# tnychron_1_3.net
KiCad netlist of a schematic drawn in EAGLE
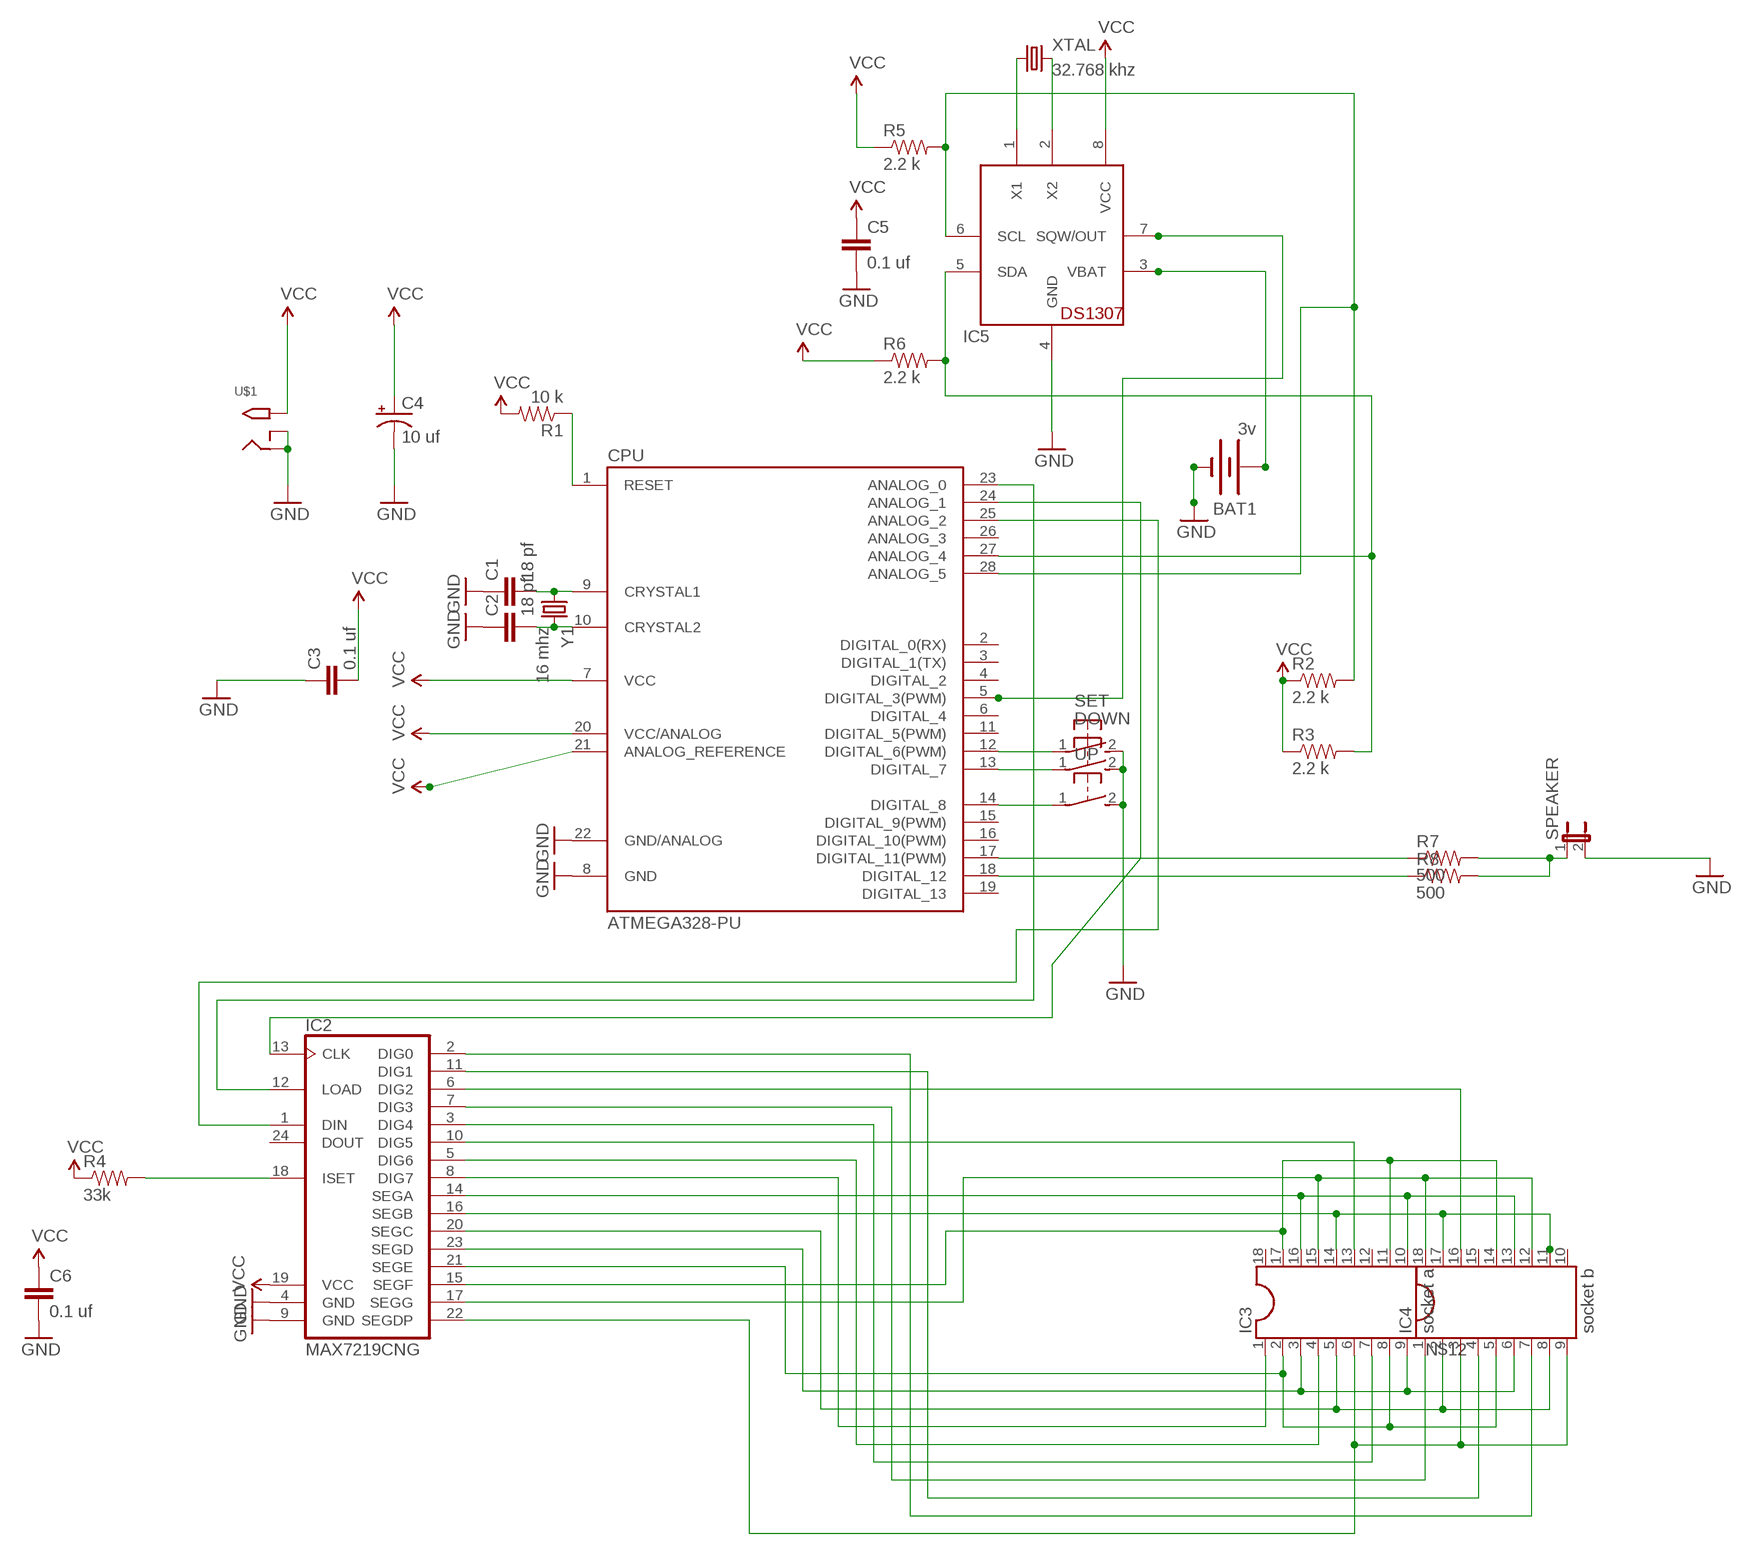
[diagram p0: schematic, sheet 1]

(export (version "E")
  (design (tool "Eeschema 10.0.6"))
  (components
    (comp (ref "BAT1")
      (value "3v")
      (footprint "eagle-import:BATTCON_12MM_PTH")
      (libsource (lib "eagle-import") (part "BATTERY12PTH"))
    )
    (comp (ref "C1")
      (value "18 pf")
      (footprint "eagle-import:CAP-PTH-SMALL2")
      (libsource (lib "eagle-import") (part "CAPPTH2"))
    )
    (comp (ref "C2")
      (value "18 pf")
      (footprint "eagle-import:CAP-PTH-SMALL2")
      (libsource (lib "eagle-import") (part "CAPPTH2"))
    )
    (comp (ref "C3")
      (value "0.1 uf")
      (footprint "eagle-import:CAP-PTH-SMALL2")
      (libsource (lib "eagle-import") (part "CAPPTH2"))
    )
    (comp (ref "C4")
      (value "10 uf")
      (footprint "eagle-import:CPOL-RADIAL-10UF-25V")
      (libsource (lib "eagle-import") (part "CAP_POLPTH2"))
    )
    (comp (ref "C5")
      (value "0.1 uf")
      (footprint "eagle-import:CAP-PTH-SMALL2")
      (libsource (lib "eagle-import") (part "CAPPTH2"))
    )
    (comp (ref "C6")
      (value "0.1 uf")
      (footprint "eagle-import:CAP-PTH-SMALL2")
      (libsource (lib "eagle-import") (part "CAPPTH2"))
    )
    (comp (ref "CPU")
      (value "ATMEGA328-PU")
      (footprint "eagle-import:DIL28-3")
      (libsource (lib "eagle-import") (part "ATMEGA168-PU"))
    )
    (comp (ref "DOWN")
      (value "31-XX")
      (footprint "eagle-import:B3F-31XX")
      (libsource (lib "eagle-import") (part "31-XX"))
    )
    (comp (ref "IC2")
      (value "MAX7219CNG")
      (footprint "eagle-import:DIL24-3")
      (fields (field (name "MF") "MAXIM"))
      (libsource (lib "eagle-import") (part "MAX7219CNG"))
    )
    (comp (ref "IC3")
      (value "socket a")
      (footprint "eagle-import:DIL18")
      (libsource (lib "eagle-import") (part "DIL18"))
    )
    (comp (ref "IC4")
      (value "socket b")
      (footprint "eagle-import:DIL18")
      (libsource (lib "eagle-import") (part "DIL18"))
    )
    (comp (ref "IC5")
      (value "DS1307")
      (footprint "eagle-import:DIL08")
      (libsource (lib "eagle-import") (part "DS1307"))
    )
    (comp (ref "R1")
      (value "10 k")
      (footprint "eagle-import:AXIAL-0.4")
      (libsource (lib "eagle-import") (part "RESISTORPTH-1/4W"))
    )
    (comp (ref "R2")
      (value "2.2 k")
      (footprint "eagle-import:AXIAL-0.4")
      (libsource (lib "eagle-import") (part "RESISTORPTH-1/4W"))
    )
    (comp (ref "R3")
      (value "2.2 k")
      (footprint "eagle-import:AXIAL-0.4")
      (libsource (lib "eagle-import") (part "RESISTORPTH-1/4W"))
    )
    (comp (ref "R4")
      (value "33k")
      (footprint "eagle-import:AXIAL-0.4")
      (libsource (lib "eagle-import") (part "RESISTORPTH-1/4W"))
    )
    (comp (ref "R5")
      (value "2.2 k")
      (footprint "eagle-import:AXIAL-0.4")
      (libsource (lib "eagle-import") (part "RESISTORPTH-1/4W"))
    )
    (comp (ref "R6")
      (value "2.2 k")
      (footprint "eagle-import:AXIAL-0.4")
      (libsource (lib "eagle-import") (part "RESISTORPTH-1/4W"))
    )
    (comp (ref "R7")
      (value "500")
      (footprint "eagle-import:AXIAL-0.3")
      (libsource (lib "eagle-import") (part "RESISTORAXIAL-0.3"))
    )
    (comp (ref "R8")
      (value "500")
      (footprint "eagle-import:AXIAL-0.3")
      (libsource (lib "eagle-import") (part "RESISTORAXIAL-0.3"))
    )
    (comp (ref "SET")
      (value "31-XX")
      (footprint "eagle-import:B3F-31XX")
      (libsource (lib "eagle-import") (part "31-XX"))
    )
    (comp (ref "SPEAKER")
      (value "JUMPER-2PTH")
      (footprint "eagle-import:1X02")
      (libsource (lib "eagle-import") (part "JUMPER-2PTH"))
    )
    (comp (ref "U$1")
      (value "2.1MMJACKTHM")
      (footprint "eagle-import:PJ-102A")
      (libsource (lib "eagle-import") (part "2.1MMJACKTHM"))
    )
    (comp (ref "UP")
      (value "31-XX")
      (footprint "eagle-import:B3F-31XX")
      (libsource (lib "eagle-import") (part "31-XX"))
    )
    (comp (ref "XTAL")
      (value "32.768 khz")
      (footprint "eagle-import:TC26H")
      (libsource (lib "eagle-import") (part "CRYSTALTC26H"))
    )
    (comp (ref "Y1")
      (value "16 mhz")
      (footprint "eagle-import:HC49US")
      (libsource (lib "eagle-import") (part "CRYSTALHC49US"))
    )
  )
  (nets
    (net (code "1") (name "/N$12") (class "Default")
      (node (ref "IC2") (pin "7") (pinfunction "DIG3_7") (pintype "output"))
      (node (ref "IC4") (pin "1") (pinfunction "1_1") (pintype "passive"))
    )
    (net (code "2") (name "GND") (class "Default")
      (node (ref "BAT1") (pin "GND") (pinfunction "-_GND") (pintype "power_in"))
      (node (ref "C1") (pin "1") (pinfunction "1_1") (pintype "passive"))
      (node (ref "C2") (pin "1") (pinfunction "1_1") (pintype "passive"))
      (node (ref "C3") (pin "1") (pinfunction "1_1") (pintype "passive"))
      (node (ref "C4") (pin "2") (pinfunction "-_2") (pintype "passive"))
      (node (ref "C5") (pin "2") (pinfunction "2_2") (pintype "passive"))
      (node (ref "C6") (pin "2") (pinfunction "2_2") (pintype "passive"))
      (node (ref "CPU") (pin "22") (pinfunction "GND/ANALOG_22") (pintype "power_in"))
      (node (ref "CPU") (pin "8") (pinfunction "GND_8") (pintype "power_in"))
      (node (ref "DOWN") (pin "2") (pinfunction "S_2") (pintype "passive"))
      (node (ref "IC2") (pin "4") (pinfunction "GND_4") (pintype "power_in"))
      (node (ref "IC2") (pin "9") (pinfunction "GND_9") (pintype "power_in"))
      (node (ref "IC5") (pin "4") (pinfunction "GND_4") (pintype "power_in"))
      (node (ref "SET") (pin "2") (pinfunction "S_2") (pintype "passive"))
      (node (ref "SPEAKER") (pin "2") (pinfunction "2_2") (pintype "passive"))
      (node (ref "U$1") (pin "RING") (pinfunction "RING_RING") (pintype "bidirectional"))
      (node (ref "U$1") (pin "RING_SW") (pinfunction "RING_SW_RING_SW") (pintype "bidirectional"))
      (node (ref "UP") (pin "2") (pinfunction "S_2") (pintype "passive"))
    )
    (net (code "3") (name "Net-(BAT1-+)") (class "Default")
      (node (ref "BAT1") (pin "VCC@1") (pinfunction "+_VCC@1") (pintype "power_in"))
      (node (ref "IC5") (pin "3") (pinfunction "VBAT_3") (pintype "power_in"))
    )
    (net (code "4") (name "Net-(CPU-ANALOG_0)") (class "Default")
      (node (ref "CPU") (pin "23") (pinfunction "ANALOG_0_23") (pintype "bidirectional"))
      (node (ref "IC2") (pin "12") (pinfunction "LOAD_12") (pintype "input"))
    )
    (net (code "5") (name "Net-(CPU-ANALOG_1)") (class "Default")
      (node (ref "CPU") (pin "24") (pinfunction "ANALOG_1_24") (pintype "bidirectional"))
      (node (ref "IC2") (pin "13") (pinfunction "CLK_13") (pintype "input"))
    )
    (net (code "6") (name "Net-(CPU-ANALOG_2)") (class "Default")
      (node (ref "CPU") (pin "25") (pinfunction "ANALOG_2_25") (pintype "bidirectional"))
      (node (ref "IC2") (pin "1") (pinfunction "DIN_1") (pintype "input"))
    )
    (net (code "7") (name "Net-(CPU-ANALOG_4)") (class "Default")
      (node (ref "CPU") (pin "27") (pinfunction "ANALOG_4_27") (pintype "bidirectional"))
      (node (ref "IC5") (pin "5") (pinfunction "SDA_5") (pintype "bidirectional"))
      (node (ref "R3") (pin "P$2") (pinfunction "2_P$2") (pintype "passive"))
      (node (ref "R6") (pin "P$2") (pinfunction "2_P$2") (pintype "passive"))
    )
    (net (code "8") (name "Net-(CPU-ANALOG_5)") (class "Default")
      (node (ref "CPU") (pin "28") (pinfunction "ANALOG_5_28") (pintype "bidirectional"))
      (node (ref "IC5") (pin "6") (pinfunction "SCL_6") (pintype "bidirectional"))
      (node (ref "R2") (pin "P$2") (pinfunction "2_P$2") (pintype "passive"))
      (node (ref "R5") (pin "P$2") (pinfunction "2_P$2") (pintype "passive"))
    )
    (net (code "9") (name "Net-(CPU-CRYSTAL1)") (class "Default")
      (node (ref "C1") (pin "2") (pinfunction "2_2") (pintype "passive"))
      (node (ref "CPU") (pin "9") (pinfunction "CRYSTAL1_9") (pintype "bidirectional"))
      (node (ref "Y1") (pin "1") (pinfunction "1_1") (pintype "passive"))
    )
    (net (code "10") (name "Net-(CPU-CRYSTAL2)") (class "Default")
      (node (ref "C2") (pin "2") (pinfunction "2_2") (pintype "passive"))
      (node (ref "CPU") (pin "10") (pinfunction "CRYSTAL2_10") (pintype "bidirectional"))
      (node (ref "Y1") (pin "2") (pinfunction "2_2") (pintype "passive"))
    )
    (net (code "11") (name "Net-(CPU-DIGITAL_3(PWM))") (class "Default")
      (node (ref "CPU") (pin "5") (pinfunction "DIGITAL_3(PWM)_5") (pintype "bidirectional"))
      (node (ref "IC5") (pin "7") (pinfunction "SQW/OUT_7") (pintype "bidirectional"))
    )
    (net (code "12") (name "Net-(CPU-DIGITAL_6(PWM))") (class "Default")
      (node (ref "CPU") (pin "12") (pinfunction "DIGITAL_6(PWM)_12") (pintype "bidirectional"))
      (node (ref "SET") (pin "1") (pinfunction "P_1") (pintype "passive"))
    )
    (net (code "13") (name "Net-(CPU-DIGITAL_7)") (class "Default")
      (node (ref "CPU") (pin "13") (pinfunction "DIGITAL_7_13") (pintype "bidirectional"))
      (node (ref "DOWN") (pin "1") (pinfunction "P_1") (pintype "passive"))
    )
    (net (code "14") (name "Net-(CPU-DIGITAL_8)") (class "Default")
      (node (ref "CPU") (pin "14") (pinfunction "DIGITAL_8_14") (pintype "bidirectional"))
      (node (ref "UP") (pin "1") (pinfunction "P_1") (pintype "passive"))
    )
    (net (code "15") (name "Net-(CPU-DIGITAL_11(PWM))") (class "Default")
      (node (ref "CPU") (pin "17") (pinfunction "DIGITAL_11(PWM)_17") (pintype "bidirectional"))
      (node (ref "R7") (pin "P$1") (pinfunction "1_P$1") (pintype "passive"))
    )
    (net (code "16") (name "Net-(CPU-DIGITAL_12)") (class "Default")
      (node (ref "CPU") (pin "18") (pinfunction "DIGITAL_12_18") (pintype "bidirectional"))
      (node (ref "R8") (pin "P$1") (pinfunction "1_P$1") (pintype "passive"))
    )
    (net (code "17") (name "Net-(CPU-RESET)") (class "Default")
      (node (ref "CPU") (pin "1") (pinfunction "RESET_1") (pintype "bidirectional"))
      (node (ref "R1") (pin "P$1") (pinfunction "1_P$1") (pintype "passive"))
    )
    (net (code "18") (name "Net-(IC2-DIG0)") (class "Default")
      (node (ref "IC2") (pin "2") (pinfunction "DIG0_2") (pintype "output"))
      (node (ref "IC4") (pin "7") (pinfunction "7_7") (pintype "passive"))
    )
    (net (code "19") (name "Net-(IC2-DIG1)") (class "Default")
      (node (ref "IC2") (pin "11") (pinfunction "DIG1_11") (pintype "output"))
      (node (ref "IC4") (pin "4") (pinfunction "4_4") (pintype "passive"))
    )
    (net (code "20") (name "Net-(IC2-DIG2)") (class "Default")
      (node (ref "IC2") (pin "6") (pinfunction "DIG2_6") (pintype "output"))
      (node (ref "IC4") (pin "16") (pinfunction "16_16") (pintype "passive"))
    )
    (net (code "21") (name "Net-(IC2-DIG4)") (class "Default")
      (node (ref "IC2") (pin "3") (pinfunction "DIG4_3") (pintype "output"))
      (node (ref "IC3") (pin "7") (pinfunction "7_7") (pintype "passive"))
    )
    (net (code "22") (name "Net-(IC2-DIG5)") (class "Default")
      (node (ref "IC2") (pin "10") (pinfunction "DIG5_10") (pintype "output"))
      (node (ref "IC3") (pin "13") (pinfunction "13_13") (pintype "passive"))
    )
    (net (code "23") (name "Net-(IC2-DIG6)") (class "Default")
      (node (ref "IC2") (pin "5") (pinfunction "DIG6_5") (pintype "output"))
      (node (ref "IC3") (pin "4") (pinfunction "4_4") (pintype "passive"))
    )
    (net (code "24") (name "Net-(IC2-DIG7)") (class "Default")
      (node (ref "IC2") (pin "8") (pinfunction "DIG7_8") (pintype "output"))
      (node (ref "IC3") (pin "1") (pinfunction "1_1") (pintype "passive"))
    )
    (net (code "25") (name "Net-(IC2-ISET)") (class "Default")
      (node (ref "IC2") (pin "18") (pinfunction "ISET_18") (pintype "input"))
      (node (ref "R4") (pin "P$2") (pinfunction "2_P$2") (pintype "passive"))
    )
    (net (code "26") (name "Net-(IC2-SEGA)") (class "Default")
      (node (ref "IC2") (pin "14") (pinfunction "SEGA_14") (pintype "output"))
      (node (ref "IC3") (pin "10") (pinfunction "10_10") (pintype "passive"))
      (node (ref "IC3") (pin "16") (pinfunction "16_16") (pintype "passive"))
      (node (ref "IC4") (pin "13") (pinfunction "13_13") (pintype "passive"))
    )
    (net (code "27") (name "Net-(IC2-SEGB)") (class "Default")
      (node (ref "IC2") (pin "16") (pinfunction "SEGB_16") (pintype "output"))
      (node (ref "IC3") (pin "14") (pinfunction "14_14") (pintype "passive"))
      (node (ref "IC4") (pin "11") (pinfunction "11_11") (pintype "passive"))
      (node (ref "IC4") (pin "17") (pinfunction "17_17") (pintype "passive"))
    )
    (net (code "28") (name "Net-(IC2-SEGC)") (class "Default")
      (node (ref "IC2") (pin "20") (pinfunction "SEGC_20") (pintype "output"))
      (node (ref "IC3") (pin "5") (pinfunction "5_5") (pintype "passive"))
      (node (ref "IC4") (pin "2") (pinfunction "2_2") (pintype "passive"))
      (node (ref "IC4") (pin "8") (pinfunction "8_8") (pintype "passive"))
    )
    (net (code "29") (name "Net-(IC2-SEGD)") (class "Default")
      (node (ref "IC2") (pin "23") (pinfunction "SEGD_23") (pintype "output"))
      (node (ref "IC3") (pin "3") (pinfunction "3_3") (pintype "passive"))
      (node (ref "IC3") (pin "9") (pinfunction "9_9") (pintype "passive"))
      (node (ref "IC4") (pin "6") (pinfunction "6_6") (pintype "passive"))
    )
    (net (code "30") (name "Net-(IC2-SEGDP)") (class "Default")
      (node (ref "IC2") (pin "22") (pinfunction "SEGDP_22") (pintype "output"))
      (node (ref "IC3") (pin "6") (pinfunction "6_6") (pintype "passive"))
      (node (ref "IC4") (pin "3") (pinfunction "3_3") (pintype "passive"))
      (node (ref "IC4") (pin "9") (pinfunction "9_9") (pintype "passive"))
    )
    (net (code "31") (name "Net-(IC2-SEGE)") (class "Default")
      (node (ref "IC2") (pin "21") (pinfunction "SEGE_21") (pintype "output"))
      (node (ref "IC3") (pin "2") (pinfunction "2_2") (pintype "passive"))
      (node (ref "IC3") (pin "8") (pinfunction "8_8") (pintype "passive"))
      (node (ref "IC4") (pin "5") (pinfunction "5_5") (pintype "passive"))
    )
    (net (code "32") (name "Net-(IC2-SEGF)") (class "Default")
      (node (ref "IC2") (pin "15") (pinfunction "SEGF_15") (pintype "output"))
      (node (ref "IC3") (pin "11") (pinfunction "11_11") (pintype "passive"))
      (node (ref "IC3") (pin "17") (pinfunction "17_17") (pintype "passive"))
      (node (ref "IC4") (pin "14") (pinfunction "14_14") (pintype "passive"))
    )
    (net (code "33") (name "Net-(IC2-SEGG)") (class "Default")
      (node (ref "IC2") (pin "17") (pinfunction "SEGG_17") (pintype "output"))
      (node (ref "IC3") (pin "15") (pinfunction "15_15") (pintype "passive"))
      (node (ref "IC4") (pin "12") (pinfunction "12_12") (pintype "passive"))
      (node (ref "IC4") (pin "18") (pinfunction "18_18") (pintype "passive"))
    )
    (net (code "34") (name "Net-(IC5-X1)") (class "Default")
      (node (ref "IC5") (pin "1") (pinfunction "X1_1") (pintype "passive"))
      (node (ref "XTAL") (pin "1") (pinfunction "1_1") (pintype "passive"))
    )
    (net (code "35") (name "Net-(IC5-X2)") (class "Default")
      (node (ref "IC5") (pin "2") (pinfunction "X2_2") (pintype "passive"))
      (node (ref "XTAL") (pin "2") (pinfunction "2_2") (pintype "passive"))
    )
    (net (code "36") (name "Net-(R7-2)") (class "Default")
      (node (ref "R7") (pin "P$2") (pinfunction "2_P$2") (pintype "passive"))
      (node (ref "R8") (pin "P$2") (pinfunction "2_P$2") (pintype "passive"))
      (node (ref "SPEAKER") (pin "1") (pinfunction "1_1") (pintype "passive"))
    )
    (net (code "37") (name "VCC") (class "Default")
      (node (ref "C3") (pin "2") (pinfunction "2_2") (pintype "passive"))
      (node (ref "C4") (pin "1") (pinfunction "+_1") (pintype "passive"))
      (node (ref "C5") (pin "1") (pinfunction "1_1") (pintype "passive"))
      (node (ref "C6") (pin "1") (pinfunction "1_1") (pintype "passive"))
      (node (ref "CPU") (pin "20") (pinfunction "VCC/ANALOG_20") (pintype "passive"))
      (node (ref "CPU") (pin "21") (pinfunction "ANALOG_REFERENCE_21") (pintype "passive"))
      (node (ref "CPU") (pin "7") (pinfunction "VCC_7") (pintype "power_in"))
      (node (ref "IC2") (pin "19") (pinfunction "VCC_19") (pintype "power_in"))
      (node (ref "IC5") (pin "8") (pinfunction "VCC_8") (pintype "power_in"))
      (node (ref "R1") (pin "P$2") (pinfunction "2_P$2") (pintype "passive"))
      (node (ref "R2") (pin "P$1") (pinfunction "1_P$1") (pintype "passive"))
      (node (ref "R3") (pin "P$1") (pinfunction "1_P$1") (pintype "passive"))
      (node (ref "R4") (pin "P$1") (pinfunction "1_P$1") (pintype "passive"))
      (node (ref "R5") (pin "P$1") (pinfunction "1_P$1") (pintype "passive"))
      (node (ref "R6") (pin "P$1") (pinfunction "1_P$1") (pintype "passive"))
      (node (ref "U$1") (pin "TIP") (pinfunction "TIP_TIP") (pintype "bidirectional"))
    )
    (net (code "38") (name "unconnected-(CPU-ANALOG_3-Pad26)") (class "Default")
      (node (ref "CPU") (pin "26") (pinfunction "ANALOG_3_26") (pintype "bidirectional"))
    )
    (net (code "39") (name "unconnected-(CPU-DIGITAL_0(RX)-Pad2)") (class "Default")
      (node (ref "CPU") (pin "2") (pinfunction "DIGITAL_0(RX)_2") (pintype "bidirectional"))
    )
    (net (code "40") (name "unconnected-(CPU-DIGITAL_1(TX)-Pad3)") (class "Default")
      (node (ref "CPU") (pin "3") (pinfunction "DIGITAL_1(TX)_3") (pintype "bidirectional"))
    )
    (net (code "41") (name "unconnected-(CPU-DIGITAL_2-Pad4)") (class "Default")
      (node (ref "CPU") (pin "4") (pinfunction "DIGITAL_2_4") (pintype "bidirectional"))
    )
    (net (code "42") (name "unconnected-(CPU-DIGITAL_4-Pad6)") (class "Default")
      (node (ref "CPU") (pin "6") (pinfunction "DIGITAL_4_6") (pintype "bidirectional"))
    )
    (net (code "43") (name "unconnected-(CPU-DIGITAL_5(PWM)-Pad11)") (class "Default")
      (node (ref "CPU") (pin "11") (pinfunction "DIGITAL_5(PWM)_11") (pintype "bidirectional"))
    )
    (net (code "44") (name "unconnected-(CPU-DIGITAL_9(PWM)-Pad15)") (class "Default")
      (node (ref "CPU") (pin "15") (pinfunction "DIGITAL_9(PWM)_15") (pintype "bidirectional"))
    )
    (net (code "45") (name "unconnected-(CPU-DIGITAL_10(PWM)-Pad16)") (class "Default")
      (node (ref "CPU") (pin "16") (pinfunction "DIGITAL_10(PWM)_16") (pintype "bidirectional"))
    )
    (net (code "46") (name "unconnected-(CPU-DIGITAL_13-Pad19)") (class "Default")
      (node (ref "CPU") (pin "19") (pinfunction "DIGITAL_13_19") (pintype "bidirectional"))
    )
    (net (code "47") (name "unconnected-(IC2-DOUT-Pad24)") (class "Default")
      (node (ref "IC2") (pin "24") (pinfunction "DOUT_24") (pintype "output"))
    )
    (net (code "48") (name "unconnected-(IC3-Pad12)") (class "Default")
      (node (ref "IC3") (pin "12") (pinfunction "12_12") (pintype "passive"))
    )
    (net (code "49") (name "unconnected-(IC3-Pad18)") (class "Default")
      (node (ref "IC3") (pin "18") (pinfunction "18_18") (pintype "passive"))
    )
    (net (code "50") (name "unconnected-(IC4-Pad10)") (class "Default")
      (node (ref "IC4") (pin "10") (pinfunction "10_10") (pintype "passive"))
    )
    (net (code "51") (name "unconnected-(IC4-Pad15)") (class "Default")
      (node (ref "IC4") (pin "15") (pinfunction "15_15") (pintype "passive"))
    )
  )
)
